# isolate.net
KiCad netlist of a schematic drawn in Altium Designer
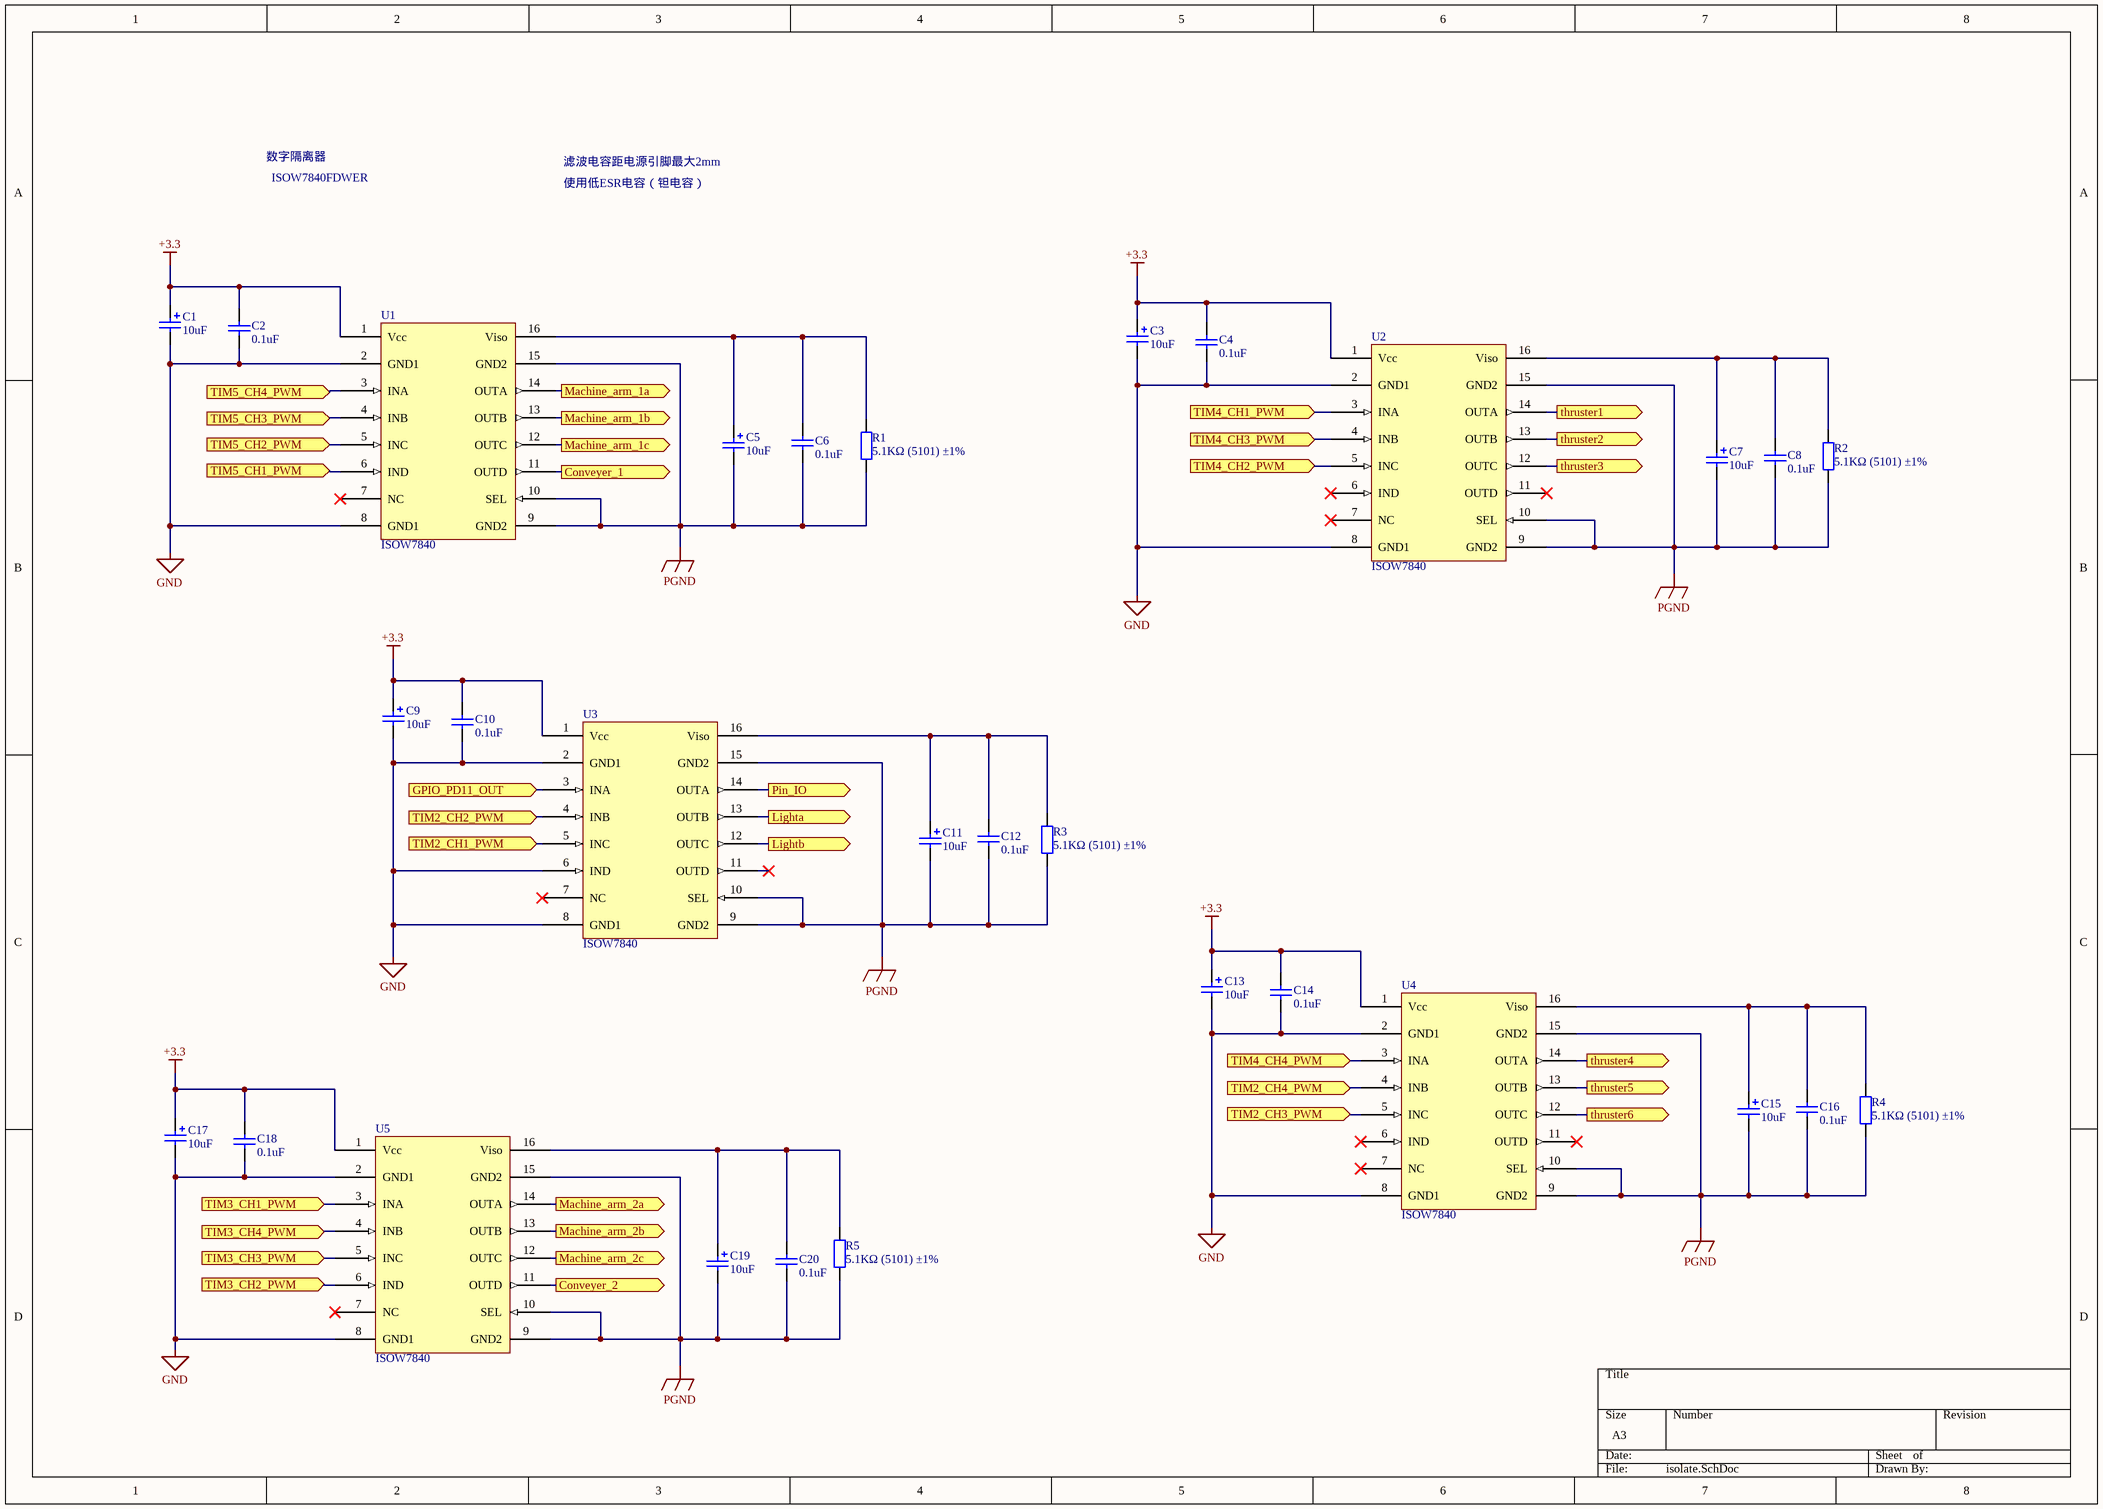
[diagram p0: isolate.SchDoc]

(export (version "E")
  (design (tool "Eeschema 10.0.6"))
  (components
    (comp (ref "C1")
      (value "10uF")
      (footprint "CASE-B_3528")
      (description "钽电容")
      (libsource (lib "Miscellaneous Devices LC") (part "3528 100uF (107) 10% 6.3V"))
    )
    (comp (ref "C2")
      (value "0.1uF")
      (footprint "0603_C")
      (description "贴片电容")
      (libsource (lib "Miscellaneous Devices LC") (part "0603 100nF (104) 10% 50V"))
    )
    (comp (ref "C3")
      (value "10uF")
      (footprint "CASE-B_3528")
      (description "钽电容")
      (libsource (lib "Miscellaneous Devices LC") (part "3528 100uF (107) 10% 6.3V"))
    )
    (comp (ref "C4")
      (value "0.1uF")
      (footprint "0603_C")
      (description "贴片电容")
      (libsource (lib "Miscellaneous Devices LC") (part "0603 100nF (104) 10% 50V"))
    )
    (comp (ref "C5")
      (value "10uF")
      (footprint "CASE-B_3528")
      (description "钽电容")
      (libsource (lib "Miscellaneous Devices LC") (part "3528 100uF (107) 10% 6.3V"))
    )
    (comp (ref "C6")
      (value "0.1uF")
      (footprint "0603_C")
      (description "贴片电容")
      (libsource (lib "Miscellaneous Devices LC") (part "0603 100nF (104) 10% 50V"))
    )
    (comp (ref "C7")
      (value "10uF")
      (footprint "CASE-B_3528")
      (description "钽电容")
      (libsource (lib "Miscellaneous Devices LC") (part "3528 100uF (107) 10% 6.3V"))
    )
    (comp (ref "C8")
      (value "0.1uF")
      (footprint "0603_C")
      (description "贴片电容")
      (libsource (lib "Miscellaneous Devices LC") (part "0603 100nF (104) 10% 50V"))
    )
    (comp (ref "C9")
      (value "10uF")
      (footprint "CASE-B_3528")
      (description "钽电容")
      (libsource (lib "Miscellaneous Devices LC") (part "3528 100uF (107) 10% 6.3V"))
    )
    (comp (ref "C10")
      (value "0.1uF")
      (footprint "0603_C")
      (description "贴片电容")
      (libsource (lib "Miscellaneous Devices LC") (part "0603 100nF (104) 10% 50V"))
    )
    (comp (ref "C11")
      (value "10uF")
      (footprint "CASE-B_3528")
      (description "钽电容")
      (libsource (lib "Miscellaneous Devices LC") (part "3528 100uF (107) 10% 6.3V"))
    )
    (comp (ref "C12")
      (value "0.1uF")
      (footprint "0603_C")
      (description "贴片电容")
      (libsource (lib "Miscellaneous Devices LC") (part "0603 100nF (104) 10% 50V"))
    )
    (comp (ref "C13")
      (value "10uF")
      (footprint "CASE-B_3528")
      (description "钽电容")
      (libsource (lib "Miscellaneous Devices LC") (part "3528 100uF (107) 10% 6.3V"))
    )
    (comp (ref "C14")
      (value "0.1uF")
      (footprint "0603_C")
      (description "贴片电容")
      (libsource (lib "Miscellaneous Devices LC") (part "0603 100nF (104) 10% 50V"))
    )
    (comp (ref "C15")
      (value "10uF")
      (footprint "CASE-B_3528")
      (description "钽电容")
      (libsource (lib "Miscellaneous Devices LC") (part "3528 100uF (107) 10% 6.3V"))
    )
    (comp (ref "C16")
      (value "0.1uF")
      (footprint "0603_C")
      (description "贴片电容")
      (libsource (lib "Miscellaneous Devices LC") (part "0603 100nF (104) 10% 50V"))
    )
    (comp (ref "C17")
      (value "10uF")
      (footprint "CASE-B_3528")
      (description "钽电容")
      (libsource (lib "Miscellaneous Devices LC") (part "3528 100uF (107) 10% 6.3V"))
    )
    (comp (ref "C18")
      (value "0.1uF")
      (footprint "0603_C")
      (description "贴片电容")
      (libsource (lib "Miscellaneous Devices LC") (part "0603 100nF (104) 10% 50V"))
    )
    (comp (ref "C19")
      (value "10uF")
      (footprint "CASE-B_3528")
      (description "钽电容")
      (libsource (lib "Miscellaneous Devices LC") (part "3528 100uF (107) 10% 6.3V"))
    )
    (comp (ref "C20")
      (value "0.1uF")
      (footprint "0603_C")
      (description "贴片电容")
      (libsource (lib "Miscellaneous Devices LC") (part "0603 100nF (104) 10% 50V"))
    )
    (comp (ref "R1")
      (value "5.1KΩ (5101) ±1%")
      (footprint "0805_R")
      (description "贴片电阻")
      (libsource (lib "Miscellaneous Devices LC") (part "0805 5.1KΩ (5101) 1%"))
    )
    (comp (ref "R2")
      (value "5.1KΩ (5101) ±1%")
      (footprint "0805_R")
      (description "贴片电阻")
      (libsource (lib "Miscellaneous Devices LC") (part "0805 5.1KΩ (5101) 1%"))
    )
    (comp (ref "R3")
      (value "5.1KΩ (5101) ±1%")
      (footprint "0805_R")
      (description "贴片电阻")
      (libsource (lib "Miscellaneous Devices LC") (part "0805 5.1KΩ (5101) 1%"))
    )
    (comp (ref "R4")
      (value "5.1KΩ (5101) ±1%")
      (footprint "0805_R")
      (description "贴片电阻")
      (libsource (lib "Miscellaneous Devices LC") (part "0805 5.1KΩ (5101) 1%"))
    )
    (comp (ref "R5")
      (value "5.1KΩ (5101) ±1%")
      (footprint "0805_R")
      (description "贴片电阻")
      (libsource (lib "Miscellaneous Devices LC") (part "0805 5.1KΩ (5101) 1%"))
    )
    (comp (ref "U1") (value "ISOW7840") (footprint "ISOW7840") (libsource (lib "Schlib1") (part "ISOW7840")))
    (comp (ref "U2") (value "ISOW7840") (footprint "ISOW7840") (libsource (lib "Schlib1") (part "ISOW7840")))
    (comp (ref "U3") (value "ISOW7840") (footprint "ISOW7840") (libsource (lib "Schlib1") (part "ISOW7840")))
    (comp (ref "U4") (value "ISOW7840") (footprint "ISOW7840") (libsource (lib "Schlib1") (part "ISOW7840")))
    (comp (ref "U5") (value "ISOW7840") (footprint "ISOW7840") (libsource (lib "Schlib1") (part "ISOW7840")))
  )
  (nets
    (net (code "1") (name "+3.3") (class "Default")
      (node (ref "C1") (pin "1") (pinfunction "1_1") (pintype "passive"))
      (node (ref "C10") (pin "2") (pinfunction "2_2") (pintype "passive"))
      (node (ref "C13") (pin "1") (pinfunction "1_1") (pintype "passive"))
      (node (ref "C14") (pin "2") (pinfunction "2_2") (pintype "passive"))
      (node (ref "C17") (pin "1") (pinfunction "1_1") (pintype "passive"))
      (node (ref "C18") (pin "2") (pinfunction "2_2") (pintype "passive"))
      (node (ref "C2") (pin "2") (pinfunction "2_2") (pintype "passive"))
      (node (ref "C3") (pin "1") (pinfunction "1_1") (pintype "passive"))
      (node (ref "C4") (pin "2") (pinfunction "2_2") (pintype "passive"))
      (node (ref "C9") (pin "1") (pinfunction "1_1") (pintype "passive"))
      (node (ref "U1") (pin "1") (pinfunction "Vcc_1") (pintype "power_in"))
      (node (ref "U2") (pin "1") (pinfunction "Vcc_1") (pintype "power_in"))
      (node (ref "U3") (pin "1") (pinfunction "Vcc_1") (pintype "power_in"))
      (node (ref "U4") (pin "1") (pinfunction "Vcc_1") (pintype "power_in"))
      (node (ref "U5") (pin "1") (pinfunction "Vcc_1") (pintype "power_in"))
    )
    (net (code "2") (name "/Conveyer_1") (class "Default")
      (node (ref "U1") (pin "11") (pinfunction "OUTD_11") (pintype "output"))
    )
    (net (code "3") (name "/Conveyer_2") (class "Default")
      (node (ref "U5") (pin "11") (pinfunction "OUTD_11") (pintype "output"))
    )
    (net (code "4") (name "/GPIO_PD11_OUT") (class "Default")
      (node (ref "U3") (pin "3") (pinfunction "INA_3") (pintype "input"))
    )
    (net (code "5") (name "/Lighta") (class "Default")
      (node (ref "U3") (pin "13") (pinfunction "OUTB_13") (pintype "output"))
    )
    (net (code "6") (name "/Lightb") (class "Default")
      (node (ref "U3") (pin "12") (pinfunction "OUTC_12") (pintype "output"))
    )
    (net (code "7") (name "/Machine_arm_1a") (class "Default")
      (node (ref "U1") (pin "14") (pinfunction "OUTA_14") (pintype "output"))
    )
    (net (code "8") (name "/Machine_arm_1b") (class "Default")
      (node (ref "U1") (pin "13") (pinfunction "OUTB_13") (pintype "output"))
    )
    (net (code "9") (name "/Machine_arm_1c") (class "Default")
      (node (ref "U1") (pin "12") (pinfunction "OUTC_12") (pintype "output"))
    )
    (net (code "10") (name "/Machine_arm_2a") (class "Default")
      (node (ref "U5") (pin "14") (pinfunction "OUTA_14") (pintype "output"))
    )
    (net (code "11") (name "/Machine_arm_2b") (class "Default")
      (node (ref "U5") (pin "13") (pinfunction "OUTB_13") (pintype "output"))
    )
    (net (code "12") (name "/Machine_arm_2c") (class "Default")
      (node (ref "U5") (pin "12") (pinfunction "OUTC_12") (pintype "output"))
    )
    (net (code "13") (name "/Pin_IO") (class "Default")
      (node (ref "U3") (pin "14") (pinfunction "OUTA_14") (pintype "output"))
    )
    (net (code "14") (name "/TIM2_CH1_PWM") (class "Default")
      (node (ref "U3") (pin "5") (pinfunction "INC_5") (pintype "input"))
    )
    (net (code "15") (name "/TIM2_CH2_PWM") (class "Default")
      (node (ref "U3") (pin "4") (pinfunction "INB_4") (pintype "input"))
    )
    (net (code "16") (name "/TIM2_CH3_PWM") (class "Default")
      (node (ref "U4") (pin "5") (pinfunction "INC_5") (pintype "input"))
    )
    (net (code "17") (name "/TIM2_CH4_PWM") (class "Default")
      (node (ref "U4") (pin "4") (pinfunction "INB_4") (pintype "input"))
    )
    (net (code "18") (name "/TIM3_CH1_PWM") (class "Default")
      (node (ref "U5") (pin "3") (pinfunction "INA_3") (pintype "input"))
    )
    (net (code "19") (name "/TIM3_CH2_PWM") (class "Default")
      (node (ref "U5") (pin "6") (pinfunction "IND_6") (pintype "input"))
    )
    (net (code "20") (name "/TIM3_CH3_PWM") (class "Default")
      (node (ref "U5") (pin "5") (pinfunction "INC_5") (pintype "input"))
    )
    (net (code "21") (name "/TIM3_CH4_PWM") (class "Default")
      (node (ref "U5") (pin "4") (pinfunction "INB_4") (pintype "input"))
    )
    (net (code "22") (name "/TIM4_CH1_PWM") (class "Default")
      (node (ref "U2") (pin "3") (pinfunction "INA_3") (pintype "input"))
    )
    (net (code "23") (name "/TIM4_CH2_PWM") (class "Default")
      (node (ref "U2") (pin "5") (pinfunction "INC_5") (pintype "input"))
    )
    (net (code "24") (name "/TIM4_CH3_PWM") (class "Default")
      (node (ref "U2") (pin "4") (pinfunction "INB_4") (pintype "input"))
    )
    (net (code "25") (name "/TIM4_CH4_PWM") (class "Default")
      (node (ref "U4") (pin "3") (pinfunction "INA_3") (pintype "input"))
    )
    (net (code "26") (name "/TIM5_CH1_PWM") (class "Default")
      (node (ref "U1") (pin "6") (pinfunction "IND_6") (pintype "input"))
    )
    (net (code "27") (name "/TIM5_CH2_PWM") (class "Default")
      (node (ref "U1") (pin "5") (pinfunction "INC_5") (pintype "input"))
    )
    (net (code "28") (name "/TIM5_CH3_PWM") (class "Default")
      (node (ref "U1") (pin "4") (pinfunction "INB_4") (pintype "input"))
    )
    (net (code "29") (name "/TIM5_CH4_PWM") (class "Default")
      (node (ref "U1") (pin "3") (pinfunction "INA_3") (pintype "input"))
    )
    (net (code "30") (name "/thruster1") (class "Default")
      (node (ref "U2") (pin "14") (pinfunction "OUTA_14") (pintype "output"))
    )
    (net (code "31") (name "/thruster2") (class "Default")
      (node (ref "U2") (pin "13") (pinfunction "OUTB_13") (pintype "output"))
    )
    (net (code "32") (name "/thruster3") (class "Default")
      (node (ref "U2") (pin "12") (pinfunction "OUTC_12") (pintype "output"))
    )
    (net (code "33") (name "/thruster4") (class "Default")
      (node (ref "U4") (pin "14") (pinfunction "OUTA_14") (pintype "output"))
    )
    (net (code "34") (name "/thruster5") (class "Default")
      (node (ref "U4") (pin "13") (pinfunction "OUTB_13") (pintype "output"))
    )
    (net (code "35") (name "/thruster6") (class "Default")
      (node (ref "U4") (pin "12") (pinfunction "OUTC_12") (pintype "output"))
    )
    (net (code "36") (name "GND") (class "Default")
      (node (ref "C1") (pin "2") (pinfunction "2_2") (pintype "passive"))
      (node (ref "C10") (pin "1") (pinfunction "1_1") (pintype "passive"))
      (node (ref "C13") (pin "2") (pinfunction "2_2") (pintype "passive"))
      (node (ref "C14") (pin "1") (pinfunction "1_1") (pintype "passive"))
      (node (ref "C17") (pin "2") (pinfunction "2_2") (pintype "passive"))
      (node (ref "C18") (pin "1") (pinfunction "1_1") (pintype "passive"))
      (node (ref "C2") (pin "1") (pinfunction "1_1") (pintype "passive"))
      (node (ref "C3") (pin "2") (pinfunction "2_2") (pintype "passive"))
      (node (ref "C4") (pin "1") (pinfunction "1_1") (pintype "passive"))
      (node (ref "C9") (pin "2") (pinfunction "2_2") (pintype "passive"))
      (node (ref "U1") (pin "2") (pinfunction "GND1_2") (pintype "power_in"))
      (node (ref "U1") (pin "8") (pinfunction "GND1_8") (pintype "power_in"))
      (node (ref "U2") (pin "2") (pinfunction "GND1_2") (pintype "power_in"))
      (node (ref "U2") (pin "8") (pinfunction "GND1_8") (pintype "power_in"))
      (node (ref "U3") (pin "2") (pinfunction "GND1_2") (pintype "power_in"))
      (node (ref "U3") (pin "6") (pinfunction "IND_6") (pintype "input"))
      (node (ref "U3") (pin "8") (pinfunction "GND1_8") (pintype "power_in"))
      (node (ref "U4") (pin "2") (pinfunction "GND1_2") (pintype "power_in"))
      (node (ref "U4") (pin "8") (pinfunction "GND1_8") (pintype "power_in"))
      (node (ref "U5") (pin "2") (pinfunction "GND1_2") (pintype "power_in"))
      (node (ref "U5") (pin "8") (pinfunction "GND1_8") (pintype "power_in"))
    )
    (net (code "37") (name "Net-(U1-Viso)") (class "Default")
      (node (ref "C5") (pin "1") (pinfunction "1_1") (pintype "passive"))
      (node (ref "C6") (pin "2") (pinfunction "2_2") (pintype "passive"))
      (node (ref "R1") (pin "2") (pinfunction "2_2") (pintype "passive"))
      (node (ref "U1") (pin "16") (pinfunction "Viso_16") (pintype "power_in"))
    )
    (net (code "38") (name "Net-(U2-Viso)") (class "Default")
      (node (ref "C7") (pin "1") (pinfunction "1_1") (pintype "passive"))
      (node (ref "C8") (pin "2") (pinfunction "2_2") (pintype "passive"))
      (node (ref "R2") (pin "2") (pinfunction "2_2") (pintype "passive"))
      (node (ref "U2") (pin "16") (pinfunction "Viso_16") (pintype "power_in"))
    )
    (net (code "39") (name "Net-(U3-Viso)") (class "Default")
      (node (ref "C11") (pin "1") (pinfunction "1_1") (pintype "passive"))
      (node (ref "C12") (pin "2") (pinfunction "2_2") (pintype "passive"))
      (node (ref "R3") (pin "2") (pinfunction "2_2") (pintype "passive"))
      (node (ref "U3") (pin "16") (pinfunction "Viso_16") (pintype "power_in"))
    )
    (net (code "40") (name "Net-(U4-Viso)") (class "Default")
      (node (ref "C15") (pin "1") (pinfunction "1_1") (pintype "passive"))
      (node (ref "C16") (pin "2") (pinfunction "2_2") (pintype "passive"))
      (node (ref "R4") (pin "2") (pinfunction "2_2") (pintype "passive"))
      (node (ref "U4") (pin "16") (pinfunction "Viso_16") (pintype "power_in"))
    )
    (net (code "41") (name "Net-(U5-Viso)") (class "Default")
      (node (ref "C19") (pin "1") (pinfunction "1_1") (pintype "passive"))
      (node (ref "C20") (pin "2") (pinfunction "2_2") (pintype "passive"))
      (node (ref "R5") (pin "2") (pinfunction "2_2") (pintype "passive"))
      (node (ref "U5") (pin "16") (pinfunction "Viso_16") (pintype "power_in"))
    )
    (net (code "42") (name "PGND") (class "Default")
      (node (ref "C11") (pin "2") (pinfunction "2_2") (pintype "passive"))
      (node (ref "C12") (pin "1") (pinfunction "1_1") (pintype "passive"))
      (node (ref "C15") (pin "2") (pinfunction "2_2") (pintype "passive"))
      (node (ref "C16") (pin "1") (pinfunction "1_1") (pintype "passive"))
      (node (ref "C19") (pin "2") (pinfunction "2_2") (pintype "passive"))
      (node (ref "C20") (pin "1") (pinfunction "1_1") (pintype "passive"))
      (node (ref "C5") (pin "2") (pinfunction "2_2") (pintype "passive"))
      (node (ref "C6") (pin "1") (pinfunction "1_1") (pintype "passive"))
      (node (ref "C7") (pin "2") (pinfunction "2_2") (pintype "passive"))
      (node (ref "C8") (pin "1") (pinfunction "1_1") (pintype "passive"))
      (node (ref "R1") (pin "1") (pinfunction "1_1") (pintype "passive"))
      (node (ref "R2") (pin "1") (pinfunction "1_1") (pintype "passive"))
      (node (ref "R3") (pin "1") (pinfunction "1_1") (pintype "passive"))
      (node (ref "R4") (pin "1") (pinfunction "1_1") (pintype "passive"))
      (node (ref "R5") (pin "1") (pinfunction "1_1") (pintype "passive"))
      (node (ref "U1") (pin "10") (pinfunction "SEL_10") (pintype "input"))
      (node (ref "U1") (pin "15") (pinfunction "GND2_15") (pintype "power_in"))
      (node (ref "U1") (pin "9") (pinfunction "GND2_9") (pintype "power_in"))
      (node (ref "U2") (pin "10") (pinfunction "SEL_10") (pintype "input"))
      (node (ref "U2") (pin "15") (pinfunction "GND2_15") (pintype "power_in"))
      (node (ref "U2") (pin "9") (pinfunction "GND2_9") (pintype "power_in"))
      (node (ref "U3") (pin "10") (pinfunction "SEL_10") (pintype "input"))
      (node (ref "U3") (pin "15") (pinfunction "GND2_15") (pintype "power_in"))
      (node (ref "U3") (pin "9") (pinfunction "GND2_9") (pintype "power_in"))
      (node (ref "U4") (pin "10") (pinfunction "SEL_10") (pintype "input"))
      (node (ref "U4") (pin "15") (pinfunction "GND2_15") (pintype "power_in"))
      (node (ref "U4") (pin "9") (pinfunction "GND2_9") (pintype "power_in"))
      (node (ref "U5") (pin "10") (pinfunction "SEL_10") (pintype "input"))
      (node (ref "U5") (pin "15") (pinfunction "GND2_15") (pintype "power_in"))
      (node (ref "U5") (pin "9") (pinfunction "GND2_9") (pintype "power_in"))
    )
    (net (code "43") (name "unconnected-(U1-NC-Pad7)") (class "Default")
      (node (ref "U1") (pin "7") (pinfunction "NC_7") (pintype "passive+no_connect"))
    )
    (net (code "44") (name "unconnected-(U2-IND-Pad6)") (class "Default")
      (node (ref "U2") (pin "6") (pinfunction "IND_6") (pintype "input+no_connect"))
    )
    (net (code "45") (name "unconnected-(U2-NC-Pad7)") (class "Default")
      (node (ref "U2") (pin "7") (pinfunction "NC_7") (pintype "passive+no_connect"))
    )
    (net (code "46") (name "unconnected-(U2-OUTD-Pad11)") (class "Default")
      (node (ref "U2") (pin "11") (pinfunction "OUTD_11") (pintype "output+no_connect"))
    )
    (net (code "47") (name "unconnected-(U3-NC-Pad7)") (class "Default")
      (node (ref "U3") (pin "7") (pinfunction "NC_7") (pintype "passive+no_connect"))
    )
    (net (code "48") (name "unconnected-(U3-OUTD-Pad11)") (class "Default")
      (node (ref "U3") (pin "11") (pinfunction "OUTD_11") (pintype "output+no_connect"))
    )
    (net (code "49") (name "unconnected-(U4-IND-Pad6)") (class "Default")
      (node (ref "U4") (pin "6") (pinfunction "IND_6") (pintype "input+no_connect"))
    )
    (net (code "50") (name "unconnected-(U4-NC-Pad7)") (class "Default")
      (node (ref "U4") (pin "7") (pinfunction "NC_7") (pintype "passive+no_connect"))
    )
    (net (code "51") (name "unconnected-(U4-OUTD-Pad11)") (class "Default")
      (node (ref "U4") (pin "11") (pinfunction "OUTD_11") (pintype "output+no_connect"))
    )
    (net (code "52") (name "unconnected-(U5-NC-Pad7)") (class "Default")
      (node (ref "U5") (pin "7") (pinfunction "NC_7") (pintype "passive+no_connect"))
    )
  )
)
